# Power_5v_3_3_ap2112k.net
KiCad netlist of a schematic drawn in EAGLE
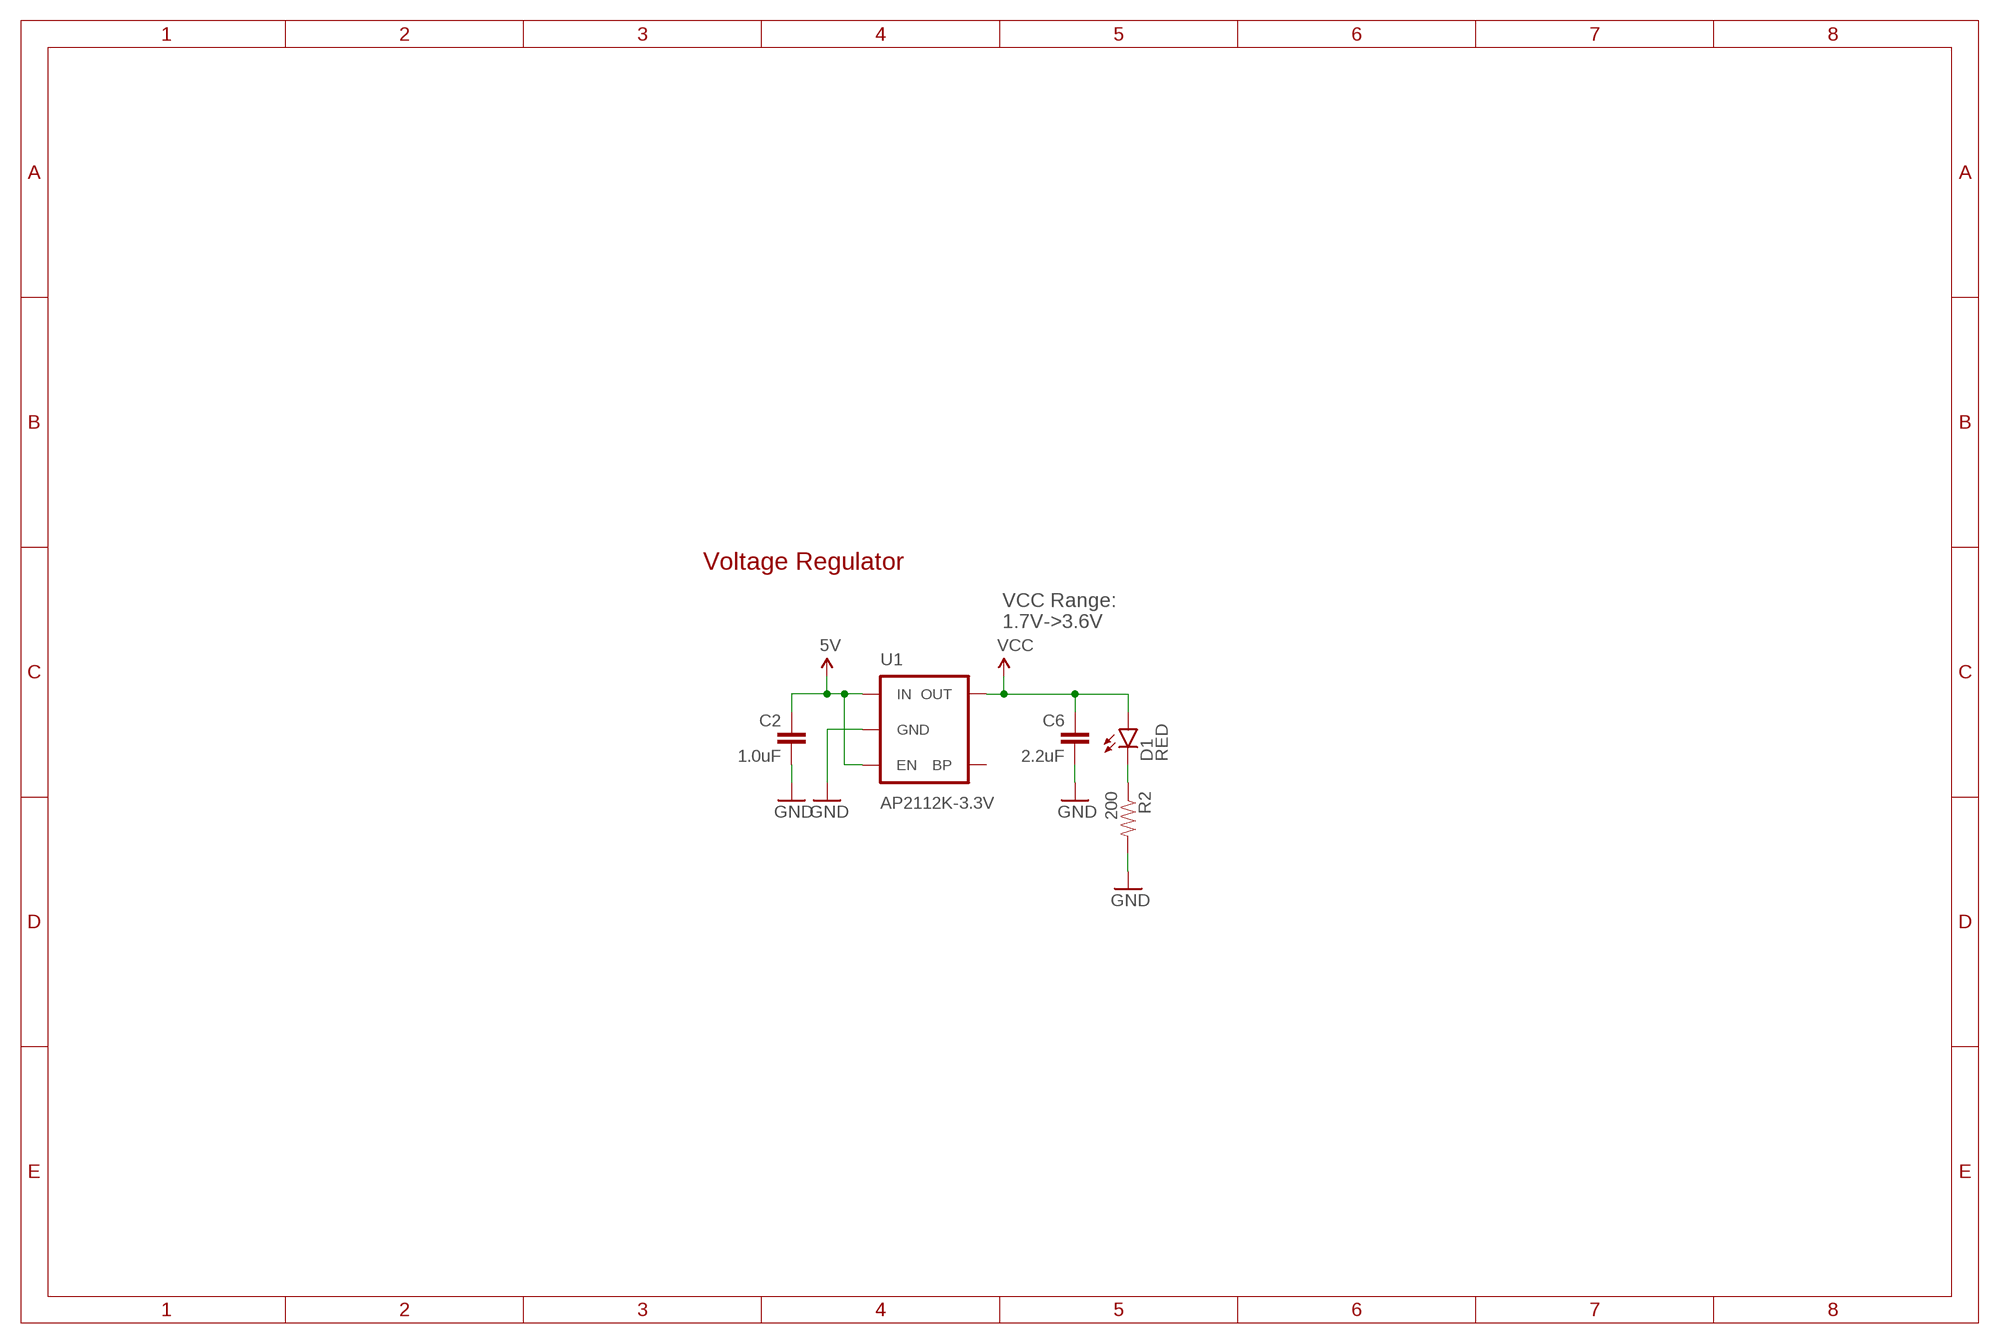
[diagram p0: schematic, sheet 1]

(export (version "E")
  (design (tool "Eeschema 10.0.6"))
  (components
    (comp (ref "C2")
      (value "1.0uF")
      (footprint "eagle-import:0805")
      (libsource (lib "eagle-import") (part "1.0UF-25V-+80/-20(0805)"))
    )
    (comp (ref "C6")
      (value "2.2uF")
      (footprint "eagle-import:0603-CAP")
      (libsource (lib "eagle-import") (part "2.2UF-10V-20%(0603)"))
    )
    (comp (ref "D1")
      (value "RED")
      (footprint "eagle-import:LED-0603")
      (libsource (lib "eagle-import") (part "LED-RED0603"))
    )
    (comp (ref "R2")
      (value "200")
      (footprint "eagle-import:0603-RES")
      (libsource (lib "eagle-import") (part "200OHM1/10W1%(0603)"))
    )
    (comp (ref "U1")
      (value "AP2112K-3.3V")
      (footprint "eagle-import:SOT23-5")
      (libsource (lib "eagle-import") (part "V_REG_LDOSMD"))
    )
  )
  (nets
    (net (code "1") (name "5V") (class "Default")
      (node (ref "C2") (pin "1") (pinfunction "1_1") (pintype "passive"))
      (node (ref "U1") (pin "1") (pinfunction "IN_1") (pintype "input"))
      (node (ref "U1") (pin "3") (pinfunction "EN_3") (pintype "input"))
    )
    (net (code "2") (name "GND") (class "Default")
      (node (ref "C2") (pin "2") (pinfunction "2_2") (pintype "passive"))
      (node (ref "C6") (pin "2") (pinfunction "2_2") (pintype "passive"))
      (node (ref "R2") (pin "2") (pinfunction "2_2") (pintype "passive"))
      (node (ref "U1") (pin "2") (pinfunction "GND_2") (pintype "input"))
    )
    (net (code "3") (name "Net-(D1-PadC)") (class "Default")
      (node (ref "D1") (pin "C") (pinfunction "C_C") (pintype "passive"))
      (node (ref "R2") (pin "1") (pinfunction "1_1") (pintype "passive"))
    )
    (net (code "4") (name "VCC") (class "Default")
      (node (ref "C6") (pin "1") (pinfunction "1_1") (pintype "passive"))
      (node (ref "D1") (pin "A") (pinfunction "A_A") (pintype "passive"))
      (node (ref "U1") (pin "5") (pinfunction "OUT_5") (pintype "passive"))
    )
    (net (code "5") (name "unconnected-(U1-BP-Pad4)") (class "Default")
      (node (ref "U1") (pin "4") (pinfunction "BP_4") (pintype "input"))
    )
  )
)
